# our_motor_driver.net
KiCad netlist of a schematic drawn in EAGLE
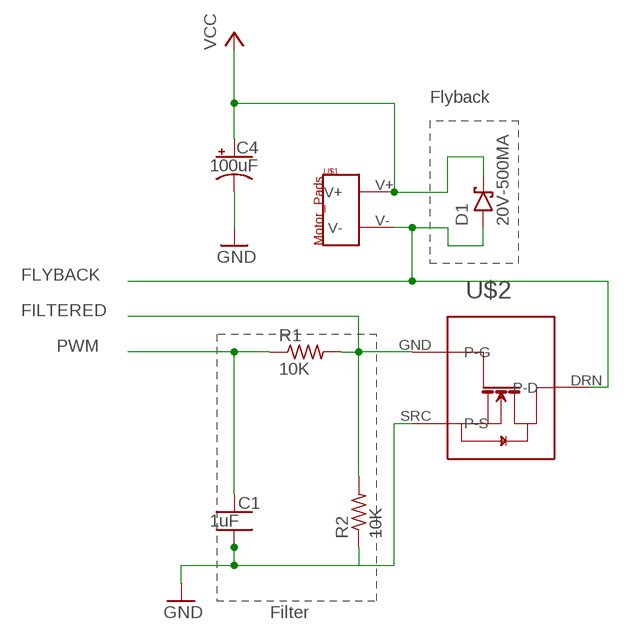
[diagram p0: schematic, sheet 1]

(export (version "E")
  (design (tool "Eeschema 10.0.6"))
  (components
    (comp (ref "C1")
      (value "1uF")
      (footprint "eagle-import:CAPC2012X140_HS")
      (fields
        (field (name "MFR") "Murata Electronics North America")
        (field (name "MPN") "GRM21BR71H105KA12L")
      )
      (libsource (lib "eagle-import") (part "CAPACITOR-NP_SMD-2012-0805_CERAMIC-1UF"))
    )
    (comp (ref "C4")
      (value "100uF")
      (footprint "eagle-import:CAPMP7343X310_HS")
      (fields (field (name "MFR") "AVX Corporation") (field (name "MPN") "TAJD227K006RNJ"))
      (libsource (lib "eagle-import") (part "CAPACITOR-POL_SMD-7043-D_TANTALUM-220UF"))
    )
    (comp (ref "D1")
      (value "20V-500MA")
      (footprint "eagle-import:SOD3716X135_HS")
      (libsource (lib "eagle-import") (part "DIODE-SCHOTTKY_SMD-SOD123"))
    )
    (comp (ref "R1")
      (value "10K")
      (footprint "eagle-import:RESC2012X60_HS")
      (fields (field (name "MFR") "Yageo") (field (name "MPN") "RC0805JR-0710KL"))
      (libsource (lib "eagle-import") (part "RESISTOR_SMD-2012-0805-10K"))
    )
    (comp (ref "R2")
      (value "10K")
      (footprint "eagle-import:RESC2012X60_HS")
      (fields (field (name "MFR") "Yageo") (field (name "MPN") "RC0805JR-0710KL"))
      (libsource (lib "eagle-import") (part "RESISTOR_SMD-2012-0805-10K"))
    )
    (comp (ref "U$1")
      (value "MOTOR_PADS")
      (footprint "eagle-import:MOTOR_PADS")
      (fields (field (name "MFR") "NA"))
      (libsource (lib "eagle-import") (part "MOTOR_PADS"))
    )
    (comp (ref "U$2")
      (value "MOSFET_20V")
      (footprint "eagle-import:MOSFET_20V")
      (fields
        (field (name "MFR") "Vishay Siliconix")
        (field (name "MPN") "SI2302CDS-T1-E3")
        (field (name "CREATOR") "Alexander Orr")
      )
      (libsource (lib "eagle-import") (part "MOSFET_20V"))
    )
  )
  (nets
    (net (code "1") (name "/FILTERED") (class "Default")
      (node (ref "R1") (pin "2") (pinfunction "2_2") (pintype "passive"))
      (node (ref "R2") (pin "2") (pinfunction "2_2") (pintype "passive"))
      (node (ref "U$2") (pin "GND") (pinfunction "P-G_GND") (pintype "passive"))
    )
    (net (code "2") (name "/FLYBACK") (class "Default")
      (node (ref "D1") (pin "A") (pinfunction "A_A") (pintype "passive"))
      (node (ref "U$1") (pin "V-") (pinfunction "V-_V-") (pintype "bidirectional"))
      (node (ref "U$2") (pin "DRN") (pinfunction "P-D_DRN") (pintype "passive"))
    )
    (net (code "3") (name "/PWM") (class "Default")
      (node (ref "C1") (pin "1") (pinfunction "1_1") (pintype "passive"))
      (node (ref "R1") (pin "1") (pinfunction "1_1") (pintype "passive"))
    )
    (net (code "4") (name "GND") (class "Default")
      (node (ref "C1") (pin "2") (pinfunction "2_2") (pintype "passive"))
      (node (ref "C4") (pin "2") (pinfunction "-_2") (pintype "passive"))
      (node (ref "R2") (pin "1") (pinfunction "1_1") (pintype "passive"))
      (node (ref "U$2") (pin "SRC") (pinfunction "P-S_SRC") (pintype "passive"))
    )
    (net (code "5") (name "VCC") (class "Default")
      (node (ref "C4") (pin "1") (pinfunction "+_1") (pintype "passive"))
      (node (ref "D1") (pin "C") (pinfunction "C_C") (pintype "passive"))
      (node (ref "U$1") (pin "V+") (pinfunction "V+_V+") (pintype "bidirectional"))
    )
  )
)
